# sensorBoard.net
KiCad netlist of a schematic drawn in EAGLE
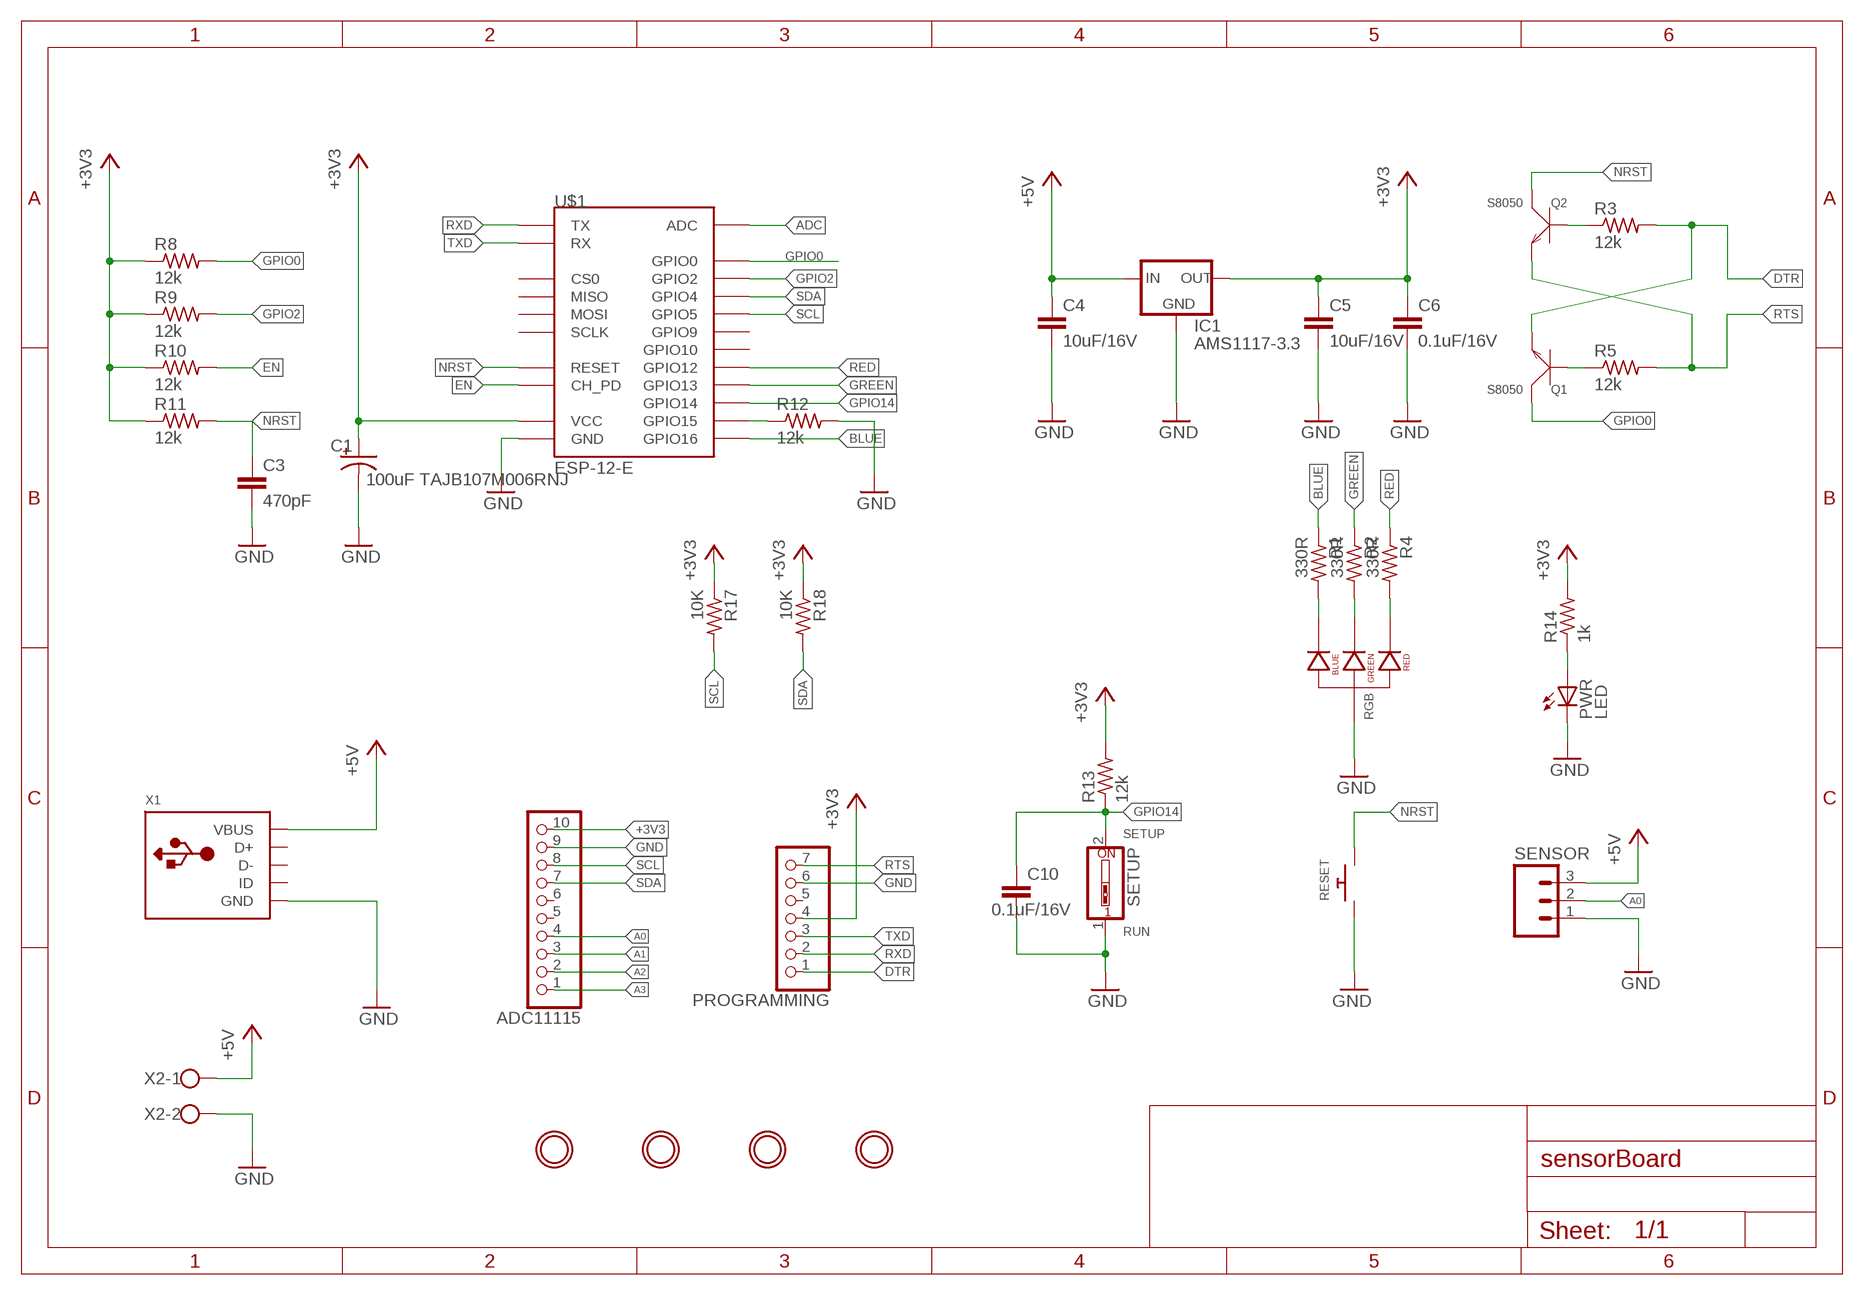
[diagram p0: schematic, sheet 1]

(export (version "E")
  (design (tool "Eeschema 10.0.6"))
  (components
    (comp (ref "ADC11115")
      (value "PINHD-1X10")
      (footprint "eagle-import:1X10")
      (libsource (lib "eagle-import") (part "PINHD-1X10"))
    )
    (comp (ref "C1")
      (value "100uF TAJB107M006RNJ")
      (footprint "eagle-import:A_3216-18R")
      (libsource (lib "eagle-import") (part "CPOL-USA/3216-18R"))
    )
    (comp (ref "C3")
      (value "470pF")
      (footprint "eagle-import:C0805K")
      (libsource (lib "eagle-import") (part "C-EUC0805K"))
    )
    (comp (ref "C4")
      (value "10uF/16V")
      (footprint "eagle-import:C0805K")
      (libsource (lib "eagle-import") (part "C-EUC0805K"))
    )
    (comp (ref "C5")
      (value "10uF/16V")
      (footprint "eagle-import:C0805K")
      (libsource (lib "eagle-import") (part "C-EUC0805K"))
    )
    (comp (ref "C6")
      (value "0.1uF/16V")
      (footprint "eagle-import:C0805K")
      (libsource (lib "eagle-import") (part "C-EUC0805K"))
    )
    (comp (ref "C10")
      (value "0.1uF/16V")
      (footprint "eagle-import:C0805K")
      (libsource (lib "eagle-import") (part "C-EUC0805K"))
    )
    (comp (ref "IC1")
      (value "AMS1117-3.3")
      (footprint "eagle-import:SOT223")
      (libsource (lib "eagle-import") (part "LM1117"))
    )
    (comp (ref "PROGRAMMING")
      (value "PINHD-1X7")
      (footprint "eagle-import:1X07")
      (libsource (lib "eagle-import") (part "PINHD-1X7"))
    )
    (comp (ref "PWR")
      (value "LED")
      (footprint "eagle-import:CHIP-LED0805")
      (libsource (lib "eagle-import") (part "LEDCHIP-LED0805"))
    )
    (comp (ref "Q1")
      (value "S8050")
      (footprint "eagle-import:SOT-23")
      (fields (field (name "MF") "JCET"))
      (libsource (lib "eagle-import") (part "SMD-TRANSISTORS-NPN-25V-500MW(SOT-23)"))
    )
    (comp (ref "Q2")
      (value "S8050")
      (footprint "eagle-import:SOT-23")
      (fields (field (name "MF") "JCET"))
      (libsource (lib "eagle-import") (part "SMD-TRANSISTORS-NPN-25V-500MW(SOT-23)"))
    )
    (comp (ref "R1")
      (value "330R")
      (footprint "eagle-import:M0805")
      (libsource (lib "eagle-import") (part "R-US_M0805"))
    )
    (comp (ref "R2")
      (value "330R")
      (footprint "eagle-import:M0805")
      (libsource (lib "eagle-import") (part "R-US_M0805"))
    )
    (comp (ref "R3")
      (value "12k")
      (footprint "eagle-import:M0805")
      (libsource (lib "eagle-import") (part "R-US_M0805"))
    )
    (comp (ref "R4")
      (value "330R")
      (footprint "eagle-import:M0805")
      (libsource (lib "eagle-import") (part "R-US_M0805"))
    )
    (comp (ref "R5")
      (value "12k")
      (footprint "eagle-import:M0805")
      (libsource (lib "eagle-import") (part "R-US_M0805"))
    )
    (comp (ref "R8")
      (value "12k")
      (footprint "eagle-import:M0805")
      (libsource (lib "eagle-import") (part "R-US_M0805"))
    )
    (comp (ref "R9")
      (value "12k")
      (footprint "eagle-import:M0805")
      (libsource (lib "eagle-import") (part "R-US_M0805"))
    )
    (comp (ref "R10")
      (value "12k")
      (footprint "eagle-import:M0805")
      (libsource (lib "eagle-import") (part "R-US_M0805"))
    )
    (comp (ref "R11")
      (value "12k")
      (footprint "eagle-import:M0805")
      (libsource (lib "eagle-import") (part "R-US_M0805"))
    )
    (comp (ref "R12")
      (value "12k")
      (footprint "eagle-import:M0805")
      (libsource (lib "eagle-import") (part "R-US_M0805"))
    )
    (comp (ref "R13")
      (value "12k")
      (footprint "eagle-import:M0805")
      (libsource (lib "eagle-import") (part "R-US_M0805"))
    )
    (comp (ref "R14")
      (value "1k")
      (footprint "eagle-import:M0805")
      (libsource (lib "eagle-import") (part "R-US_M0805"))
    )
    (comp (ref "R17")
      (value "10K")
      (footprint "eagle-import:M0805")
      (libsource (lib "eagle-import") (part "R-US_M0805"))
    )
    (comp (ref "R18")
      (value "10K")
      (footprint "eagle-import:M0805")
      (libsource (lib "eagle-import") (part "R-US_M0805"))
    )
    (comp (ref "RESET")
      (value "SWITCH_PUSHBUTTONEVQ-PE")
      (footprint "eagle-import:TACT_PANA-EVQ")
      (libsource (lib "eagle-import") (part "SWITCH_PUSHBUTTONEVQ-PE"))
    )
    (comp (ref "RGB")
      (value "LED-RGB-CA-THRUCLEAR")
      (footprint "eagle-import:LED-RGB-THRU")
      (libsource (lib "eagle-import") (part "LED-RGB-CA-THRUCLEAR"))
    )
    (comp (ref "SENSOR")
      (value "M03JST-PTH-VERT")
      (footprint "eagle-import:JST-3-PTH-VERT")
      (libsource (lib "eagle-import") (part "M03JST-PTH-VERT"))
    )
    (comp (ref "SETUP")
      (value "SW_DIP-1")
      (footprint "eagle-import:EDG-01")
      (libsource (lib "eagle-import") (part "SW_DIP-1"))
    )
    (comp (ref "U$1")
      (value "ESP-12-E")
      (footprint "eagle-import:ESP-12-E")
      (libsource (lib "eagle-import") (part "ESP-12-E"))
    )
    (comp (ref "U$3")
      (value "MOUNTINGHOLE2.5")
      (footprint "eagle-import:MOUNTINGHOLE_2.5_PLATED")
      (libsource (lib "eagle-import") (part "MOUNTINGHOLE2.5"))
    )
    (comp (ref "U$4")
      (value "MOUNTINGHOLE2.5")
      (footprint "eagle-import:MOUNTINGHOLE_2.5_PLATED")
      (libsource (lib "eagle-import") (part "MOUNTINGHOLE2.5"))
    )
    (comp (ref "U$5")
      (value "MOUNTINGHOLE2.5")
      (footprint "eagle-import:MOUNTINGHOLE_2.5_PLATED")
      (libsource (lib "eagle-import") (part "MOUNTINGHOLE2.5"))
    )
    (comp (ref "U$6")
      (value "MOUNTINGHOLE2.5")
      (footprint "eagle-import:MOUNTINGHOLE_2.5_PLATED")
      (libsource (lib "eagle-import") (part "MOUNTINGHOLE2.5"))
    )
    (comp (ref "X1")
      (value "USB_MICRO_20329_V2")
      (footprint "eagle-import:4UCONN_20329_V2")
      (libsource (lib "eagle-import") (part "USB_MICRO_20329_V2"))
    )
    (comp (ref "X2")
      (value "W237-102")
      (footprint "eagle-import:W237-102")
      (fields (field (name "MPN") "237-102"))
      (libsource (lib "eagle-import") (part "W237-102"))
    )
  )
  (nets
    (net (code "1") (name "+3V3") (class "Default")
      (node (ref "ADC11115") (pin "10") (pinfunction "10_10") (pintype "passive"))
      (node (ref "C1") (pin "+") (pinfunction "+_+") (pintype "passive"))
      (node (ref "C5") (pin "1") (pinfunction "1_1") (pintype "passive"))
      (node (ref "C6") (pin "1") (pinfunction "1_1") (pintype "passive"))
      (node (ref "IC1") (pin "2") (pinfunction "OUT_2") (pintype "passive"))
      (node (ref "PROGRAMMING") (pin "4") (pinfunction "4_4") (pintype "passive"))
      (node (ref "R10") (pin "1") (pinfunction "1_1") (pintype "passive"))
      (node (ref "R11") (pin "1") (pinfunction "1_1") (pintype "passive"))
      (node (ref "R13") (pin "2") (pinfunction "2_2") (pintype "passive"))
      (node (ref "R14") (pin "2") (pinfunction "2_2") (pintype "passive"))
      (node (ref "R17") (pin "1") (pinfunction "1_1") (pintype "passive"))
      (node (ref "R18") (pin "1") (pinfunction "1_1") (pintype "passive"))
      (node (ref "R8") (pin "1") (pinfunction "1_1") (pintype "passive"))
      (node (ref "R9") (pin "1") (pinfunction "1_1") (pintype "passive"))
      (node (ref "U$1") (pin "VCC") (pinfunction "VCC_VCC") (pintype "bidirectional"))
    )
    (net (code "2") (name "+5V") (class "Default")
      (node (ref "C4") (pin "1") (pinfunction "1_1") (pintype "passive"))
      (node (ref "IC1") (pin "3") (pinfunction "IN_3") (pintype "input"))
      (node (ref "SENSOR") (pin "3") (pinfunction "3_3") (pintype "passive"))
      (node (ref "X1") (pin "VBUS") (pinfunction "VBUS_VBUS") (pintype "power_in"))
      (node (ref "X2") (pin "1") (pinfunction "KL_1") (pintype "passive"))
    )
    (net (code "3") (name "A0") (class "Default")
      (node (ref "ADC11115") (pin "4") (pinfunction "4_4") (pintype "passive"))
      (node (ref "SENSOR") (pin "2") (pinfunction "2_2") (pintype "passive"))
    )
    (net (code "4") (name "A1") (class "Default")
      (node (ref "ADC11115") (pin "3") (pinfunction "3_3") (pintype "passive"))
    )
    (net (code "5") (name "A2") (class "Default")
      (node (ref "ADC11115") (pin "2") (pinfunction "2_2") (pintype "passive"))
    )
    (net (code "6") (name "A3") (class "Default")
      (node (ref "ADC11115") (pin "1") (pinfunction "1_1") (pintype "passive"))
    )
    (net (code "7") (name "ADC") (class "Default")
      (node (ref "U$1") (pin "ADC") (pinfunction "ADC_ADC") (pintype "bidirectional"))
    )
    (net (code "8") (name "BLUE") (class "Default")
      (node (ref "R1") (pin "1") (pinfunction "1_1") (pintype "passive"))
      (node (ref "U$1") (pin "GPIO16") (pinfunction "GPIO16_GPIO16") (pintype "bidirectional"))
    )
    (net (code "9") (name "DTR") (class "Default")
      (node (ref "PROGRAMMING") (pin "1") (pinfunction "1_1") (pintype "passive"))
      (node (ref "Q1") (pin "2") (pinfunction "E_2") (pintype "passive"))
      (node (ref "R3") (pin "2") (pinfunction "2_2") (pintype "passive"))
    )
    (net (code "10") (name "EN") (class "Default")
      (node (ref "R10") (pin "2") (pinfunction "2_2") (pintype "passive"))
      (node (ref "U$1") (pin "CH_PD") (pinfunction "CH_PD_CH_PD") (pintype "bidirectional"))
    )
    (net (code "11") (name "GND") (class "Default")
      (node (ref "ADC11115") (pin "9") (pinfunction "9_9") (pintype "passive"))
      (node (ref "C1") (pin "-") (pinfunction "-_-") (pintype "passive"))
      (node (ref "C10") (pin "2") (pinfunction "2_2") (pintype "passive"))
      (node (ref "C3") (pin "2") (pinfunction "2_2") (pintype "passive"))
      (node (ref "C4") (pin "2") (pinfunction "2_2") (pintype "passive"))
      (node (ref "C5") (pin "2") (pinfunction "2_2") (pintype "passive"))
      (node (ref "C6") (pin "2") (pinfunction "2_2") (pintype "passive"))
      (node (ref "IC1") (pin "1") (pinfunction "GND_1") (pintype "input"))
      (node (ref "PROGRAMMING") (pin "6") (pinfunction "6_6") (pintype "passive"))
      (node (ref "PWR") (pin "C") (pinfunction "C_C") (pintype "passive"))
      (node (ref "R12") (pin "2") (pinfunction "2_2") (pintype "passive"))
      (node (ref "RESET") (pin "P$1") (pinfunction "P$1_P$1") (pintype "passive"))
      (node (ref "RGB") (pin "2") (pinfunction "ANODE_2") (pintype "bidirectional"))
      (node (ref "SENSOR") (pin "1") (pinfunction "1_1") (pintype "passive"))
      (node (ref "SETUP") (pin "1") (pinfunction "1_1") (pintype "passive"))
      (node (ref "U$1") (pin "GND") (pinfunction "GND_GND") (pintype "bidirectional"))
      (node (ref "X1") (pin "BASE@1") (pinfunction "GND_BASE@1") (pintype "power_in"))
      (node (ref "X1") (pin "BASE@2") (pinfunction "GND_BASE@2") (pintype "power_in"))
      (node (ref "X1") (pin "GND") (pinfunction "GND_GND") (pintype "power_in"))
      (node (ref "X1") (pin "SPRT@1") (pinfunction "GND_SPRT@1") (pintype "power_in"))
      (node (ref "X1") (pin "SPRT@2") (pinfunction "GND_SPRT@2") (pintype "power_in"))
      (node (ref "X1") (pin "SPRT@3") (pinfunction "GND_SPRT@3") (pintype "power_in"))
      (node (ref "X1") (pin "SPRT@4") (pinfunction "GND_SPRT@4") (pintype "power_in"))
      (node (ref "X2") (pin "2") (pinfunction "KL_2") (pintype "passive"))
    )
    (net (code "12") (name "GPIO0") (class "Default")
      (node (ref "Q1") (pin "3") (pinfunction "C_3") (pintype "passive"))
      (node (ref "R8") (pin "2") (pinfunction "2_2") (pintype "passive"))
      (node (ref "U$1") (pin "GPIO0") (pinfunction "GPIO0_GPIO0") (pintype "bidirectional"))
    )
    (net (code "13") (name "GPIO2") (class "Default")
      (node (ref "R9") (pin "2") (pinfunction "2_2") (pintype "passive"))
      (node (ref "U$1") (pin "GPIO2") (pinfunction "GPIO2_GPIO2") (pintype "bidirectional"))
    )
    (net (code "14") (name "GPIO14") (class "Default")
      (node (ref "C10") (pin "1") (pinfunction "1_1") (pintype "passive"))
      (node (ref "R13") (pin "1") (pinfunction "1_1") (pintype "passive"))
      (node (ref "SETUP") (pin "2") (pinfunction "2_2") (pintype "passive"))
      (node (ref "U$1") (pin "GPIO14") (pinfunction "GPIO14_GPIO14") (pintype "bidirectional"))
    )
    (net (code "15") (name "GREEN") (class "Default")
      (node (ref "R2") (pin "1") (pinfunction "1_1") (pintype "passive"))
      (node (ref "U$1") (pin "GPIO13") (pinfunction "GPIO13_GPIO13") (pintype "bidirectional"))
    )
    (net (code "16") (name "NRST") (class "Default")
      (node (ref "C3") (pin "1") (pinfunction "1_1") (pintype "passive"))
      (node (ref "Q2") (pin "3") (pinfunction "C_3") (pintype "passive"))
      (node (ref "R11") (pin "2") (pinfunction "2_2") (pintype "passive"))
      (node (ref "RESET") (pin "P$2") (pinfunction "P$2_P$2") (pintype "passive"))
      (node (ref "U$1") (pin "RESET") (pinfunction "RESET_RESET") (pintype "bidirectional"))
    )
    (net (code "17") (name "Net-(PWR-PadA)") (class "Default")
      (node (ref "PWR") (pin "A") (pinfunction "A_A") (pintype "passive"))
      (node (ref "R14") (pin "1") (pinfunction "1_1") (pintype "passive"))
    )
    (net (code "18") (name "Net-(Q1-B)") (class "Default")
      (node (ref "Q1") (pin "1") (pinfunction "B_1") (pintype "passive"))
      (node (ref "R5") (pin "1") (pinfunction "1_1") (pintype "passive"))
    )
    (net (code "19") (name "Net-(Q2-B)") (class "Default")
      (node (ref "Q2") (pin "1") (pinfunction "B_1") (pintype "passive"))
      (node (ref "R3") (pin "1") (pinfunction "1_1") (pintype "passive"))
    )
    (net (code "20") (name "Net-(R12-Pad1)") (class "Default")
      (node (ref "R12") (pin "1") (pinfunction "1_1") (pintype "passive"))
      (node (ref "U$1") (pin "GPIO15") (pinfunction "GPIO15_GPIO15") (pintype "bidirectional"))
    )
    (net (code "21") (name "Net-(RGB-BLUE_CATHODE)") (class "Default")
      (node (ref "R1") (pin "2") (pinfunction "2_2") (pintype "passive"))
      (node (ref "RGB") (pin "4") (pinfunction "BLUE_CATHODE_4") (pintype "bidirectional"))
    )
    (net (code "22") (name "Net-(RGB-GREEN_CATHODE)") (class "Default")
      (node (ref "R2") (pin "2") (pinfunction "2_2") (pintype "passive"))
      (node (ref "RGB") (pin "3") (pinfunction "GREEN_CATHODE_3") (pintype "bidirectional"))
    )
    (net (code "23") (name "Net-(RGB-RED_CATHODE)") (class "Default")
      (node (ref "R4") (pin "2") (pinfunction "2_2") (pintype "passive"))
      (node (ref "RGB") (pin "1") (pinfunction "RED_CATHODE_1") (pintype "bidirectional"))
    )
    (net (code "24") (name "RED") (class "Default")
      (node (ref "R4") (pin "1") (pinfunction "1_1") (pintype "passive"))
      (node (ref "U$1") (pin "GPIO12") (pinfunction "GPIO12_GPIO12") (pintype "bidirectional"))
    )
    (net (code "25") (name "RTS") (class "Default")
      (node (ref "PROGRAMMING") (pin "7") (pinfunction "7_7") (pintype "passive"))
      (node (ref "Q2") (pin "2") (pinfunction "E_2") (pintype "passive"))
      (node (ref "R5") (pin "2") (pinfunction "2_2") (pintype "passive"))
    )
    (net (code "26") (name "RXD") (class "Default")
      (node (ref "PROGRAMMING") (pin "2") (pinfunction "2_2") (pintype "passive"))
      (node (ref "U$1") (pin "TX") (pinfunction "TX_TX") (pintype "bidirectional"))
    )
    (net (code "27") (name "SCL") (class "Default")
      (node (ref "ADC11115") (pin "8") (pinfunction "8_8") (pintype "passive"))
      (node (ref "R17") (pin "2") (pinfunction "2_2") (pintype "passive"))
      (node (ref "U$1") (pin "GPIO5") (pinfunction "GPIO5_GPIO5") (pintype "bidirectional"))
    )
    (net (code "28") (name "SDA") (class "Default")
      (node (ref "ADC11115") (pin "7") (pinfunction "7_7") (pintype "passive"))
      (node (ref "R18") (pin "2") (pinfunction "2_2") (pintype "passive"))
      (node (ref "U$1") (pin "GPIO4") (pinfunction "GPIO4_GPIO4") (pintype "bidirectional"))
    )
    (net (code "29") (name "TXD") (class "Default")
      (node (ref "PROGRAMMING") (pin "3") (pinfunction "3_3") (pintype "passive"))
      (node (ref "U$1") (pin "RX") (pinfunction "RX_RX") (pintype "bidirectional"))
    )
    (net (code "30") (name "unconnected-(ADC11115-Pad5)") (class "Default")
      (node (ref "ADC11115") (pin "5") (pinfunction "5_5") (pintype "passive"))
    )
    (net (code "31") (name "unconnected-(ADC11115-Pad6)") (class "Default")
      (node (ref "ADC11115") (pin "6") (pinfunction "6_6") (pintype "passive"))
    )
    (net (code "32") (name "unconnected-(PROGRAMMING-Pad5)") (class "Default")
      (node (ref "PROGRAMMING") (pin "5") (pinfunction "5_5") (pintype "passive"))
    )
    (net (code "33") (name "unconnected-(U$1-PadCS0)") (class "Default")
      (node (ref "U$1") (pin "CS0") (pinfunction "CS0_CS0") (pintype "bidirectional"))
    )
    (net (code "34") (name "unconnected-(U$1-PadGPIO9)") (class "Default")
      (node (ref "U$1") (pin "GPIO9") (pinfunction "GPIO9_GPIO9") (pintype "bidirectional"))
    )
    (net (code "35") (name "unconnected-(U$1-PadGPIO10)") (class "Default")
      (node (ref "U$1") (pin "GPIO10") (pinfunction "GPIO10_GPIO10") (pintype "bidirectional"))
    )
    (net (code "36") (name "unconnected-(U$1-PadMISO)") (class "Default")
      (node (ref "U$1") (pin "MISO") (pinfunction "MISO_MISO") (pintype "bidirectional"))
    )
    (net (code "37") (name "unconnected-(U$1-PadMOSI)") (class "Default")
      (node (ref "U$1") (pin "MOSI") (pinfunction "MOSI_MOSI") (pintype "bidirectional"))
    )
    (net (code "38") (name "unconnected-(U$1-PadSCLK)") (class "Default")
      (node (ref "U$1") (pin "SCLK") (pinfunction "SCLK_SCLK") (pintype "bidirectional"))
    )
    (net (code "39") (name "unconnected-(X1-PadD+)") (class "Default")
      (node (ref "X1") (pin "D+") (pinfunction "D+_D+") (pintype "bidirectional"))
    )
    (net (code "40") (name "unconnected-(X1-PadD-)") (class "Default")
      (node (ref "X1") (pin "D-") (pinfunction "D-_D-") (pintype "bidirectional"))
    )
    (net (code "41") (name "unconnected-(X1-PadID)") (class "Default")
      (node (ref "X1") (pin "ID") (pinfunction "ID_ID") (pintype "bidirectional"))
    )
  )
)
